# Connectors.net
KiCad netlist of a schematic drawn in Altium Designer
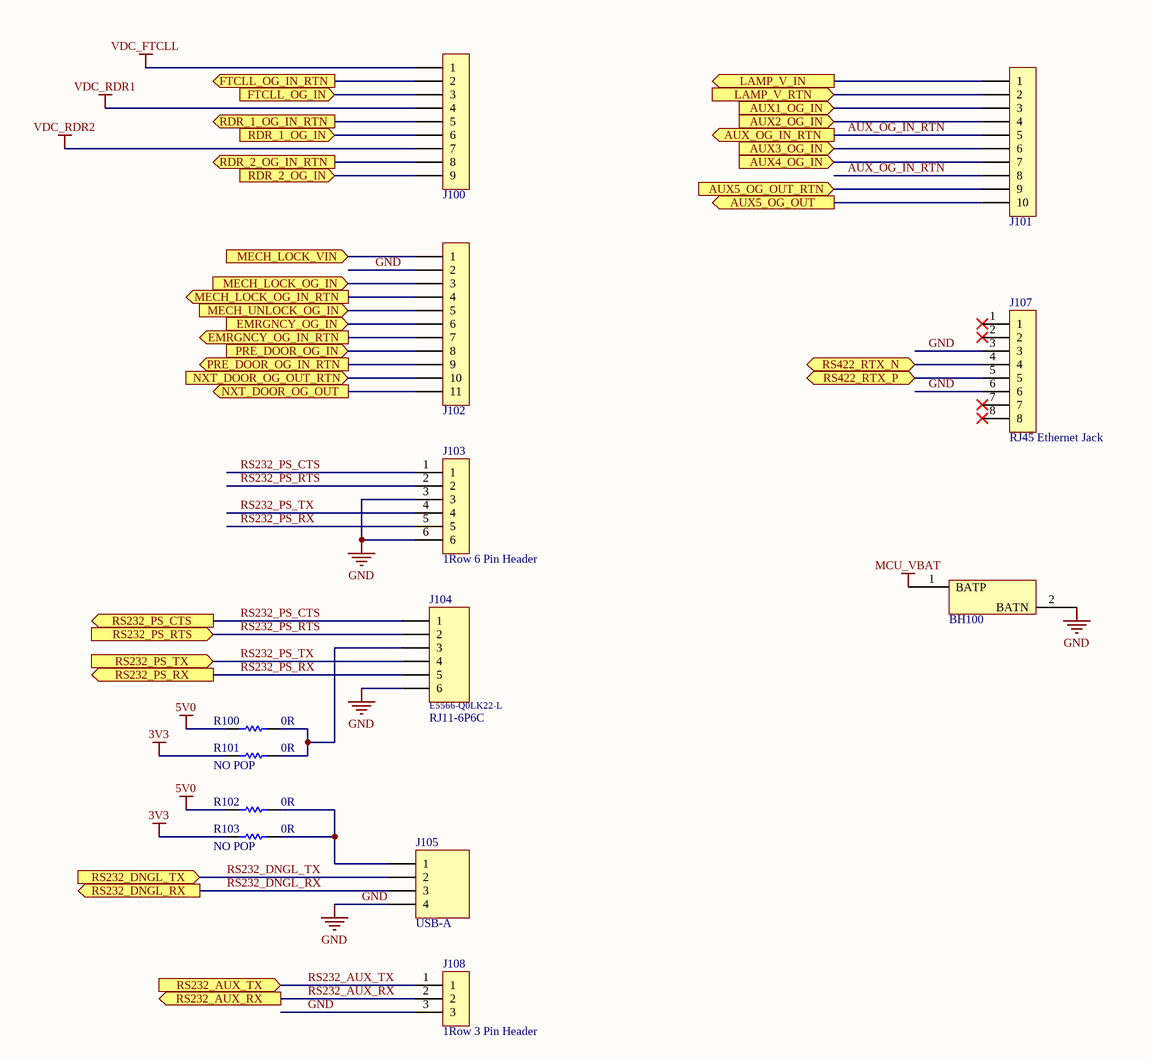
[diagram p0: Connectors.SchDoc]

(export (version "E")
  (design (tool "Eeschema 10.0.6"))
  (components
    (comp (ref "BH100")
      (value "Battery Holder")
      (footprint "AE17-020T-2032-0101")
      (description "Battery Holder, 1xCoin 20, 2032, TH, V")
      (fields (field (name "MANUFACTURER") "MPD") (field (name "MANUFACTURER PART NUMBER") "BC2032-E2"))
      (libsource (lib "Anime_Electromechanical") (part "AE17-020T-2032-0101"))
    )
    (comp (ref "J100")
      (value "~")
      (footprint "AJ61-1009-TAPR-RNS0")
      (description "CON, Terminal, Klemens, 9 Pins, 1-Row, 5.08mm, TH, P, R")
      (fields
        (field (name "MANUFACTURER") "ON-SHORE")
        (field (name "MANUFACTURER PART NUMBER") "OSTOQ095451")
      )
      (libsource (lib "Anime_Connector") (part "AJ61-1009-TAPR-RNS0"))
    )
    (comp (ref "J101")
      (value "~")
      (footprint "AJ61-1010-TAPR-RNS0")
      (description "CON, Terminal, Klemens, 10 Pins, 1-Row, 5.08mm, TH, P, R")
      (fields
        (field (name "MANUFACTURER") "ON-SHORE")
        (field (name "MANUFACTURER PART NUMBER") "OSTOQ105451")
      )
      (libsource (lib "Anime_Connector") (part "AJ61-1010-TAPR-RNS0"))
    )
    (comp (ref "J102")
      (value "~")
      (footprint "AJ61-1011-TAPR-RNS0")
      (description "CON, Terminal, Klemens, 11 Pins, 1-Row, 5.08mm, TH, P, R")
      (fields
        (field (name "MANUFACTURER") "ON-SHORE")
        (field (name "MANUFACTURER PART NUMBER") "OSTOQ115451")
      )
      (libsource (lib "Anime_Connector") (part "AJ61-1011-TAPR-RNS0"))
    )
    (comp (ref "J103")
      (value "1Row 6 Pin Header")
      (footprint "AJ23-1006-T8P0-VFC0")
      (description "CON, W2B, 6 Pins, 1-Row, 2.54mm, TH, P, VER")
      (fields (field (name "MANUFACTURER") "FCI") (field (name "MANUFACTURER PART NUMBER") "68001-206HLF"))
      (libsource (lib "Anime_Connector") (part "AJ23-1006-T8P0-VFC0"))
    )
    (comp (ref "J104")
      (value "RJ11-6P6C")
      (footprint "AJ31-1006-TKSR-RPU0")
      (description "CON, Jack, 6P6C, 1 Row, 6 Pins, 1.02 mm, TH, S, RA")
      (fields
        (field (name "MANUFACTURER") "Pulse")
        (field (name "MANUFACTURER PART NUMBER") "E5566-Q0LK22-L")
      )
      (libsource (lib "Anime_Connector") (part "AJ31-1006-TKSR-RPU0"))
    )
    (comp (ref "J105")
      (value "USB-A")
      (footprint "AJA1-1004-TJSR-RAM0")
      (description "CON, USB, 4 pins, RA, TH")
      (fields
        (field (name "MANUFACTURER") "Amphenol Commercial")
        (field (name "MANUFACTURER PART NUMBER") "UE27AC54100")
      )
      (libsource (lib "Anime_Connector") (part "AJA1-1004-TJSR-RAM0"))
    )
    (comp (ref "J107")
      (value "RJ45 Ethernet Jack")
      (footprint "AJ32-1008-SD70-RTE0")
      (description "CON, Jack, 8 Pins, 1-Row, 0.61mm, SMD, S, RA")
      (fields
        (field (name "MANUFACTURER") "TE Connectivity")
        (field (name "MANUFACTURER PART NUMBER") "5406721-2")
      )
      (libsource (lib "Anime_Connector") (part "AJ32-1008-SD70-RTE0"))
    )
    (comp (ref "J108")
      (value "1Row 3 Pin Header")
      (footprint "AJ23-1003-T8P0-VFC0")
      (description "CON, W2B, 3 Pins, 1-Row, 2.54mm, TH, P, VER")
      (fields (field (name "MANUFACTURER") "FCI") (field (name "MANUFACTURER PART NUMBER") "68001-203HLF"))
      (libsource (lib "Anime_Connector") (part "AJ23-1003-T8P0-VFC0"))
    )
    (comp (ref "R100")
      (value "0R")
      (footprint "RESC1005X04N")
      (description "RES, Thick Film, SMD, 0R, Jumper, 0.1W, 0402")
      (fields
        (field (name "MANUFACTURER") "Panasonic")
        (field (name "MANUFACTURER PART NUMBER") "ERJ-2GE0R00X")
      )
      (libsource (lib "Anime_Resistor") (part "AR19-0000-S201-0000"))
    )
    (comp (ref "R101")
      (value "0R")
      (footprint "RESC1005X04N")
      (description "RES, Thick Film, SMD, 0R, Jumper, 0.1W, 0402")
      (fields
        (field (name "MANUFACTURER") "Panasonic")
        (field (name "MANUFACTURER PART NUMBER") "ERJ-2GE0R00X")
        (field (name "ASSEMBLY") "NO POP")
      )
      (libsource (lib "Anime_Resistor") (part "AR19-0000-S201-0000"))
    )
    (comp (ref "R102")
      (value "0R")
      (footprint "RESC1005X04N")
      (description "RES, Thick Film, SMD, 0R, Jumper, 0.1W, 0402")
      (fields
        (field (name "MANUFACTURER") "Panasonic")
        (field (name "MANUFACTURER PART NUMBER") "ERJ-2GE0R00X")
      )
      (libsource (lib "Anime_Resistor") (part "AR19-0000-S201-0000"))
    )
    (comp (ref "R103")
      (value "0R")
      (footprint "RESC1005X04N")
      (description "RES, Thick Film, SMD, 0R, Jumper, 0.1W, 0402")
      (fields
        (field (name "MANUFACTURER") "Panasonic")
        (field (name "MANUFACTURER PART NUMBER") "ERJ-2GE0R00X")
        (field (name "ASSEMBLY") "NO POP")
      )
      (libsource (lib "Anime_Resistor") (part "AR19-0000-S201-0000"))
    )
  )
  (nets
    (net (code "1") (name "/AUX1_OG_IN") (class "Default")
      (node (ref "J101") (pin "3") (pinfunction "3_3") (pintype "passive"))
    )
    (net (code "2") (name "/AUX2_OG_IN") (class "Default")
      (node (ref "J101") (pin "4") (pinfunction "4_4") (pintype "passive"))
    )
    (net (code "3") (name "/AUX3_OG_IN") (class "Default")
      (node (ref "J101") (pin "6") (pinfunction "6_6") (pintype "passive"))
    )
    (net (code "4") (name "/AUX4_OG_IN") (class "Default")
      (node (ref "J101") (pin "7") (pinfunction "7_7") (pintype "passive"))
    )
    (net (code "5") (name "/AUX5_OG_OUT") (class "Default")
      (node (ref "J101") (pin "10") (pinfunction "10_10") (pintype "passive"))
    )
    (net (code "6") (name "/AUX5_OG_OUT_RTN") (class "Default")
      (node (ref "J101") (pin "9") (pinfunction "9_9") (pintype "passive"))
    )
    (net (code "7") (name "/AUX_OG_IN_RTN") (class "Default")
      (node (ref "J101") (pin "5") (pinfunction "5_5") (pintype "passive"))
      (node (ref "J101") (pin "8") (pinfunction "8_8") (pintype "passive"))
    )
    (net (code "8") (name "/EMRGNCY_OG_IN") (class "Default")
      (node (ref "J102") (pin "6") (pinfunction "6_6") (pintype "passive"))
    )
    (net (code "9") (name "/EMRGNCY_OG_IN_RTN") (class "Default")
      (node (ref "J102") (pin "7") (pinfunction "7_7") (pintype "passive"))
    )
    (net (code "10") (name "/FTCLL_OG_IN") (class "Default")
      (node (ref "J100") (pin "3") (pinfunction "3_3") (pintype "passive"))
    )
    (net (code "11") (name "/FTCLL_OG_IN_RTN") (class "Default")
      (node (ref "J100") (pin "2") (pinfunction "2_2") (pintype "passive"))
    )
    (net (code "12") (name "/LAMP_V_IN") (class "Default")
      (node (ref "J101") (pin "1") (pinfunction "1_1") (pintype "passive"))
    )
    (net (code "13") (name "/LAMP_V_RTN") (class "Default")
      (node (ref "J101") (pin "2") (pinfunction "2_2") (pintype "passive"))
    )
    (net (code "14") (name "/MECH_LOCK_OG_IN") (class "Default")
      (node (ref "J102") (pin "3") (pinfunction "3_3") (pintype "passive"))
    )
    (net (code "15") (name "/MECH_LOCK_OG_IN_RTN") (class "Default")
      (node (ref "J102") (pin "4") (pinfunction "4_4") (pintype "passive"))
    )
    (net (code "16") (name "/MECH_LOCK_VIN") (class "Default")
      (node (ref "J102") (pin "1") (pinfunction "1_1") (pintype "passive"))
    )
    (net (code "17") (name "/MECH_UNLOCK_OG_IN") (class "Default")
      (node (ref "J102") (pin "5") (pinfunction "5_5") (pintype "passive"))
    )
    (net (code "18") (name "/NXT_DOOR_OG_OUT") (class "Default")
      (node (ref "J102") (pin "11") (pinfunction "11_11") (pintype "passive"))
    )
    (net (code "19") (name "/NXT_DOOR_OG_OUT_RTN") (class "Default")
      (node (ref "J102") (pin "10") (pinfunction "10_10") (pintype "passive"))
    )
    (net (code "20") (name "/PRE_DOOR_OG_IN") (class "Default")
      (node (ref "J102") (pin "8") (pinfunction "8_8") (pintype "passive"))
    )
    (net (code "21") (name "/PRE_DOOR_OG_IN_RTN") (class "Default")
      (node (ref "J102") (pin "9") (pinfunction "9_9") (pintype "passive"))
    )
    (net (code "22") (name "/RDR_1_OG_IN") (class "Default")
      (node (ref "J100") (pin "6") (pinfunction "6_6") (pintype "passive"))
    )
    (net (code "23") (name "/RDR_1_OG_IN_RTN") (class "Default")
      (node (ref "J100") (pin "5") (pinfunction "5_5") (pintype "passive"))
    )
    (net (code "24") (name "/RDR_2_OG_IN") (class "Default")
      (node (ref "J100") (pin "9") (pinfunction "9_9") (pintype "passive"))
    )
    (net (code "25") (name "/RDR_2_OG_IN_RTN") (class "Default")
      (node (ref "J100") (pin "8") (pinfunction "8_8") (pintype "passive"))
    )
    (net (code "26") (name "/RS232_AUX_RX") (class "Default")
      (node (ref "J108") (pin "2") (pinfunction "2_2") (pintype "passive"))
    )
    (net (code "27") (name "/RS232_AUX_TX") (class "Default")
      (node (ref "J108") (pin "1") (pinfunction "1_1") (pintype "passive"))
    )
    (net (code "28") (name "/RS232_DNGL_RX") (class "Default")
      (node (ref "J105") (pin "3") (pinfunction "3_3") (pintype "passive"))
    )
    (net (code "29") (name "/RS232_DNGL_TX") (class "Default")
      (node (ref "J105") (pin "2") (pinfunction "2_2") (pintype "passive"))
    )
    (net (code "30") (name "/RS232_PS_CTS") (class "Default")
      (node (ref "J103") (pin "1") (pinfunction "1_1") (pintype "passive"))
      (node (ref "J104") (pin "1") (pinfunction "1_1") (pintype "passive"))
    )
    (net (code "31") (name "/RS232_PS_RTS") (class "Default")
      (node (ref "J103") (pin "2") (pinfunction "2_2") (pintype "passive"))
      (node (ref "J104") (pin "2") (pinfunction "2_2") (pintype "passive"))
    )
    (net (code "32") (name "/RS232_PS_RX") (class "Default")
      (node (ref "J103") (pin "5") (pinfunction "5_5") (pintype "passive"))
      (node (ref "J104") (pin "5") (pinfunction "5_5") (pintype "passive"))
    )
    (net (code "33") (name "/RS232_PS_TX") (class "Default")
      (node (ref "J103") (pin "4") (pinfunction "4_4") (pintype "passive"))
      (node (ref "J104") (pin "4") (pinfunction "4_4") (pintype "passive"))
    )
    (net (code "34") (name "/RS422_RTX_N") (class "Default")
      (node (ref "J107") (pin "4") (pinfunction "4_4") (pintype "passive"))
    )
    (net (code "35") (name "/RS422_RTX_P") (class "Default")
      (node (ref "J107") (pin "5") (pinfunction "5_5") (pintype "passive"))
    )
    (net (code "36") (name "3V3") (class "Default")
      (node (ref "R101") (pin "1") (pinfunction "1_1") (pintype "passive"))
      (node (ref "R103") (pin "1") (pinfunction "1_1") (pintype "passive"))
    )
    (net (code "37") (name "5V0") (class "Default")
      (node (ref "R100") (pin "1") (pinfunction "1_1") (pintype "passive"))
      (node (ref "R102") (pin "1") (pinfunction "1_1") (pintype "passive"))
    )
    (net (code "38") (name "GND") (class "Default")
      (node (ref "BH100") (pin "2") (pinfunction "BATN_2") (pintype "power_in"))
      (node (ref "J102") (pin "2") (pinfunction "2_2") (pintype "passive"))
      (node (ref "J103") (pin "3") (pinfunction "3_3") (pintype "passive"))
      (node (ref "J103") (pin "6") (pinfunction "6_6") (pintype "passive"))
      (node (ref "J104") (pin "6") (pinfunction "6_6") (pintype "passive"))
      (node (ref "J105") (pin "4") (pinfunction "4_4") (pintype "passive"))
      (node (ref "J107") (pin "3") (pinfunction "3_3") (pintype "passive"))
      (node (ref "J107") (pin "6") (pinfunction "6_6") (pintype "passive"))
      (node (ref "J108") (pin "3") (pinfunction "3_3") (pintype "passive"))
    )
    (net (code "39") (name "MCU_VBAT") (class "Default")
      (node (ref "BH100") (pin "1") (pinfunction "BATP_1") (pintype "power_in"))
    )
    (net (code "40") (name "Net-(J104-Pad3)") (class "Default")
      (node (ref "J104") (pin "3") (pinfunction "3_3") (pintype "passive"))
      (node (ref "R100") (pin "2") (pinfunction "2_2") (pintype "passive"))
      (node (ref "R101") (pin "2") (pinfunction "2_2") (pintype "passive"))
    )
    (net (code "41") (name "Net-(J105-Pad1)") (class "Default")
      (node (ref "J105") (pin "1") (pinfunction "1_1") (pintype "passive"))
      (node (ref "R102") (pin "2") (pinfunction "2_2") (pintype "passive"))
      (node (ref "R103") (pin "2") (pinfunction "2_2") (pintype "passive"))
    )
    (net (code "42") (name "VDC_FTCLL") (class "Default")
      (node (ref "J100") (pin "1") (pinfunction "1_1") (pintype "passive"))
    )
    (net (code "43") (name "VDC_RDR1") (class "Default")
      (node (ref "J100") (pin "4") (pinfunction "4_4") (pintype "passive"))
    )
    (net (code "44") (name "VDC_RDR2") (class "Default")
      (node (ref "J100") (pin "7") (pinfunction "7_7") (pintype "passive"))
    )
    (net (code "45") (name "unconnected-(J107-Pad1)") (class "Default")
      (node (ref "J107") (pin "1") (pinfunction "1_1") (pintype "passive+no_connect"))
    )
    (net (code "46") (name "unconnected-(J107-Pad2)") (class "Default")
      (node (ref "J107") (pin "2") (pinfunction "2_2") (pintype "passive+no_connect"))
    )
    (net (code "47") (name "unconnected-(J107-Pad7)") (class "Default")
      (node (ref "J107") (pin "7") (pinfunction "7_7") (pintype "passive+no_connect"))
    )
    (net (code "48") (name "unconnected-(J107-Pad8)") (class "Default")
      (node (ref "J107") (pin "8") (pinfunction "8_8") (pintype "passive+no_connect"))
    )
  )
)
